# Candidacy_part_1.net
KiCad netlist of a schematic drawn in EAGLE
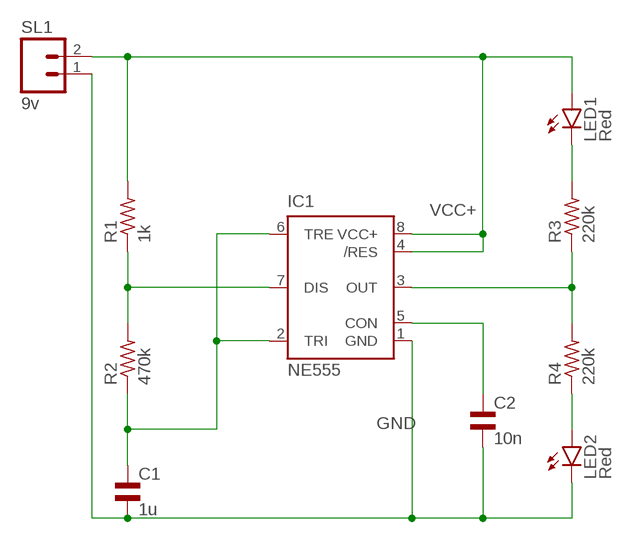
[diagram p0: schematic, sheet 1]

(export (version "E")
  (design (tool "Eeschema 10.0.6"))
  (components
    (comp (ref "C1")
      (value "1u")
      (footprint "eagle-import:EU25-10")
      (libsource (lib "eagle-import") (part "EL-BI25-10AXIAL"))
    )
    (comp (ref "C2")
      (value "10n")
      (footprint "eagle-import:EU25-10")
      (libsource (lib "eagle-import") (part "EL-BI25-10AXIAL"))
    )
    (comp (ref "IC1")
      (value "NE555")
      (footprint "eagle-import:DIL-08")
      (fields (field (name "MF") "Arrow Electronics") (field (name "MPN") "NE555N"))
      (libsource (lib "eagle-import") (part "NE555"))
    )
    (comp (ref "LED1")
      (value "Red")
      (footprint "eagle-import:LED5MM")
      (libsource (lib "eagle-import") (part "LED5MM"))
    )
    (comp (ref "LED2")
      (value "Red")
      (footprint "eagle-import:LED5MM")
      (libsource (lib "eagle-import") (part "LED5MM"))
    )
    (comp (ref "R1")
      (value "1k")
      (footprint "eagle-import:0204V")
      (libsource (lib "eagle-import") (part "R-US_0204/2V"))
    )
    (comp (ref "R2")
      (value "470k")
      (footprint "eagle-import:0204V")
      (libsource (lib "eagle-import") (part "R-US_0204/2V"))
    )
    (comp (ref "R3")
      (value "220k")
      (footprint "eagle-import:0204V")
      (libsource (lib "eagle-import") (part "R-US_0204/2V"))
    )
    (comp (ref "R4")
      (value "220k")
      (footprint "eagle-import:0204V")
      (libsource (lib "eagle-import") (part "R-US_0204/2V"))
    )
    (comp (ref "SL1")
      (value "9v")
      (footprint "eagle-import:02P")
      (libsource (lib "eagle-import") (part "M02"))
    )
  )
  (nets
    (net (code "1") (name "/GND") (class "Default")
      (node (ref "C1") (pin "2") (pinfunction "2_2") (pintype "passive"))
      (node (ref "C2") (pin "2") (pinfunction "2_2") (pintype "passive"))
      (node (ref "IC1") (pin "1") (pinfunction "GND_1") (pintype "power_in"))
      (node (ref "LED2") (pin "K") (pinfunction "C_K") (pintype "passive"))
      (node (ref "SL1") (pin "1") (pinfunction "1_1") (pintype "passive"))
    )
    (net (code "2") (name "/VCC+") (class "Default")
      (node (ref "IC1") (pin "4") (pinfunction "/RES_4") (pintype "input"))
      (node (ref "IC1") (pin "8") (pinfunction "VCC+_8") (pintype "power_in"))
      (node (ref "LED1") (pin "A") (pinfunction "A_A") (pintype "passive"))
      (node (ref "R1") (pin "2") (pinfunction "2_2") (pintype "passive"))
      (node (ref "SL1") (pin "2") (pinfunction "2_2") (pintype "passive"))
    )
    (net (code "3") (name "Net-(IC1-CON)") (class "Default")
      (node (ref "C2") (pin "1") (pinfunction "1_1") (pintype "passive"))
      (node (ref "IC1") (pin "5") (pinfunction "CON_5") (pintype "input"))
    )
    (net (code "4") (name "Net-(IC1-DIS)") (class "Default")
      (node (ref "IC1") (pin "7") (pinfunction "DIS_7") (pintype "input"))
      (node (ref "R1") (pin "1") (pinfunction "1_1") (pintype "passive"))
      (node (ref "R2") (pin "2") (pinfunction "2_2") (pintype "passive"))
    )
    (net (code "5") (name "Net-(IC1-OUT)") (class "Default")
      (node (ref "IC1") (pin "3") (pinfunction "OUT_3") (pintype "output"))
      (node (ref "R3") (pin "1") (pinfunction "1_1") (pintype "passive"))
      (node (ref "R4") (pin "2") (pinfunction "2_2") (pintype "passive"))
    )
    (net (code "6") (name "Net-(IC1-TRE)") (class "Default")
      (node (ref "C1") (pin "1") (pinfunction "1_1") (pintype "passive"))
      (node (ref "IC1") (pin "2") (pinfunction "TRI_2") (pintype "input"))
      (node (ref "IC1") (pin "6") (pinfunction "TRE_6") (pintype "input"))
      (node (ref "R2") (pin "1") (pinfunction "1_1") (pintype "passive"))
    )
    (net (code "7") (name "Net-(LED1-C)") (class "Default")
      (node (ref "LED1") (pin "K") (pinfunction "C_K") (pintype "passive"))
      (node (ref "R3") (pin "2") (pinfunction "2_2") (pintype "passive"))
    )
    (net (code "8") (name "Net-(LED2-PadA)") (class "Default")
      (node (ref "LED2") (pin "A") (pinfunction "A_A") (pintype "passive"))
      (node (ref "R4") (pin "1") (pinfunction "1_1") (pintype "passive"))
    )
  )
)
